# Reset.net
KiCad netlist of a schematic drawn in Altium Designer
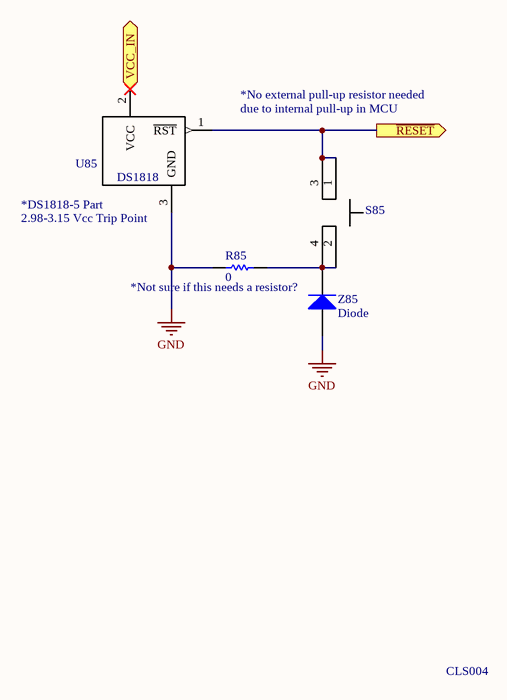
[diagram p0: Reset.SchDoc]

(export (version "E")
  (design (tool "Eeschema 10.0.6"))
  (components
    (comp (ref "R85")
      (value "0")
      (footprint "0603_CHIP_FP")
      (fields
        (field (name "MANUFACTURER") "Vishay Dale")
        (field (name "MANUFACTURER PART NUMBER") "CRCW08050000Z0EA")
        (field (name "VENDOR PART NUMBER") "541-0.0ACT-ND")
      )
      (libsource (lib "GenericSymbols") (part "Resistor_0603"))
    )
    (comp (ref "S85")
      (value "Switch")
      (footprint "Pushbutton")
      (description "Pushbutton Switch")
      (fields (field (name "MANUFACTURER") "APEM Inc.") (field (name "MANUFACTURER PART NUMBER") "MJTP1230"))
      (libsource (lib "GenericSymbols") (part "Pushbutton"))
    )
    (comp (ref "U85")
      (value "DS1818")
      (footprint "SOT95P240X110-3N")
      (description "3.3V EconoReset with Pushbutton")
      (fields
        (field (name "MANUFACTURER") "Maxim Integrated")
        (field (name "MANUFACTURER PART NUMBER") "DS1818R-5+T&R")
      )
      (libsource (lib "DS1818") (part "DS1818_5"))
    )
    (comp (ref "Z85")
      (value "Diode")
      (footprint "0603_CHIP_FP")
      (description "Default Diode")
      (fields
        (field (name "MANUFACTURER") "STMicroelectronics")
        (field (name "MANUFACTURER PART NUMBER") "ESDA7P120-1U1M")
      )
      (libsource (lib "GenericSymbols") (part "Diode"))
    )
  )
  (nets
    (net (code "1") (name "/VCC_IN") (class "Default")
      (node (ref "U85") (pin "2") (pinfunction "VCC_2") (pintype "power_in+no_connect"))
    )
    (net (code "2") (name "/~{RESET}") (class "Default")
      (node (ref "S85") (pin "1") (pintype "passive"))
      (node (ref "S85") (pin "3") (pintype "passive"))
      (node (ref "U85") (pin "1") (pinfunction "~{RST}_1") (pintype "output"))
    )
    (net (code "3") (name "GND") (class "Default")
      (node (ref "R85") (pin "1") (pinfunction "1_1") (pintype "passive"))
      (node (ref "U85") (pin "3") (pinfunction "GND_3") (pintype "power_in"))
      (node (ref "Z85") (pin "2") (pinfunction "Cathode_2") (pintype "passive"))
    )
    (net (code "4") (name "Net-(Z85-Anode)") (class "Default")
      (node (ref "R85") (pin "2") (pinfunction "2_2") (pintype "passive"))
      (node (ref "S85") (pin "2") (pintype "passive"))
      (node (ref "S85") (pin "4") (pintype "passive"))
      (node (ref "Z85") (pin "1") (pinfunction "Anode_1") (pintype "passive"))
    )
  )
)
